# motherboard.net
KiCad netlist of a schematic drawn in EAGLE
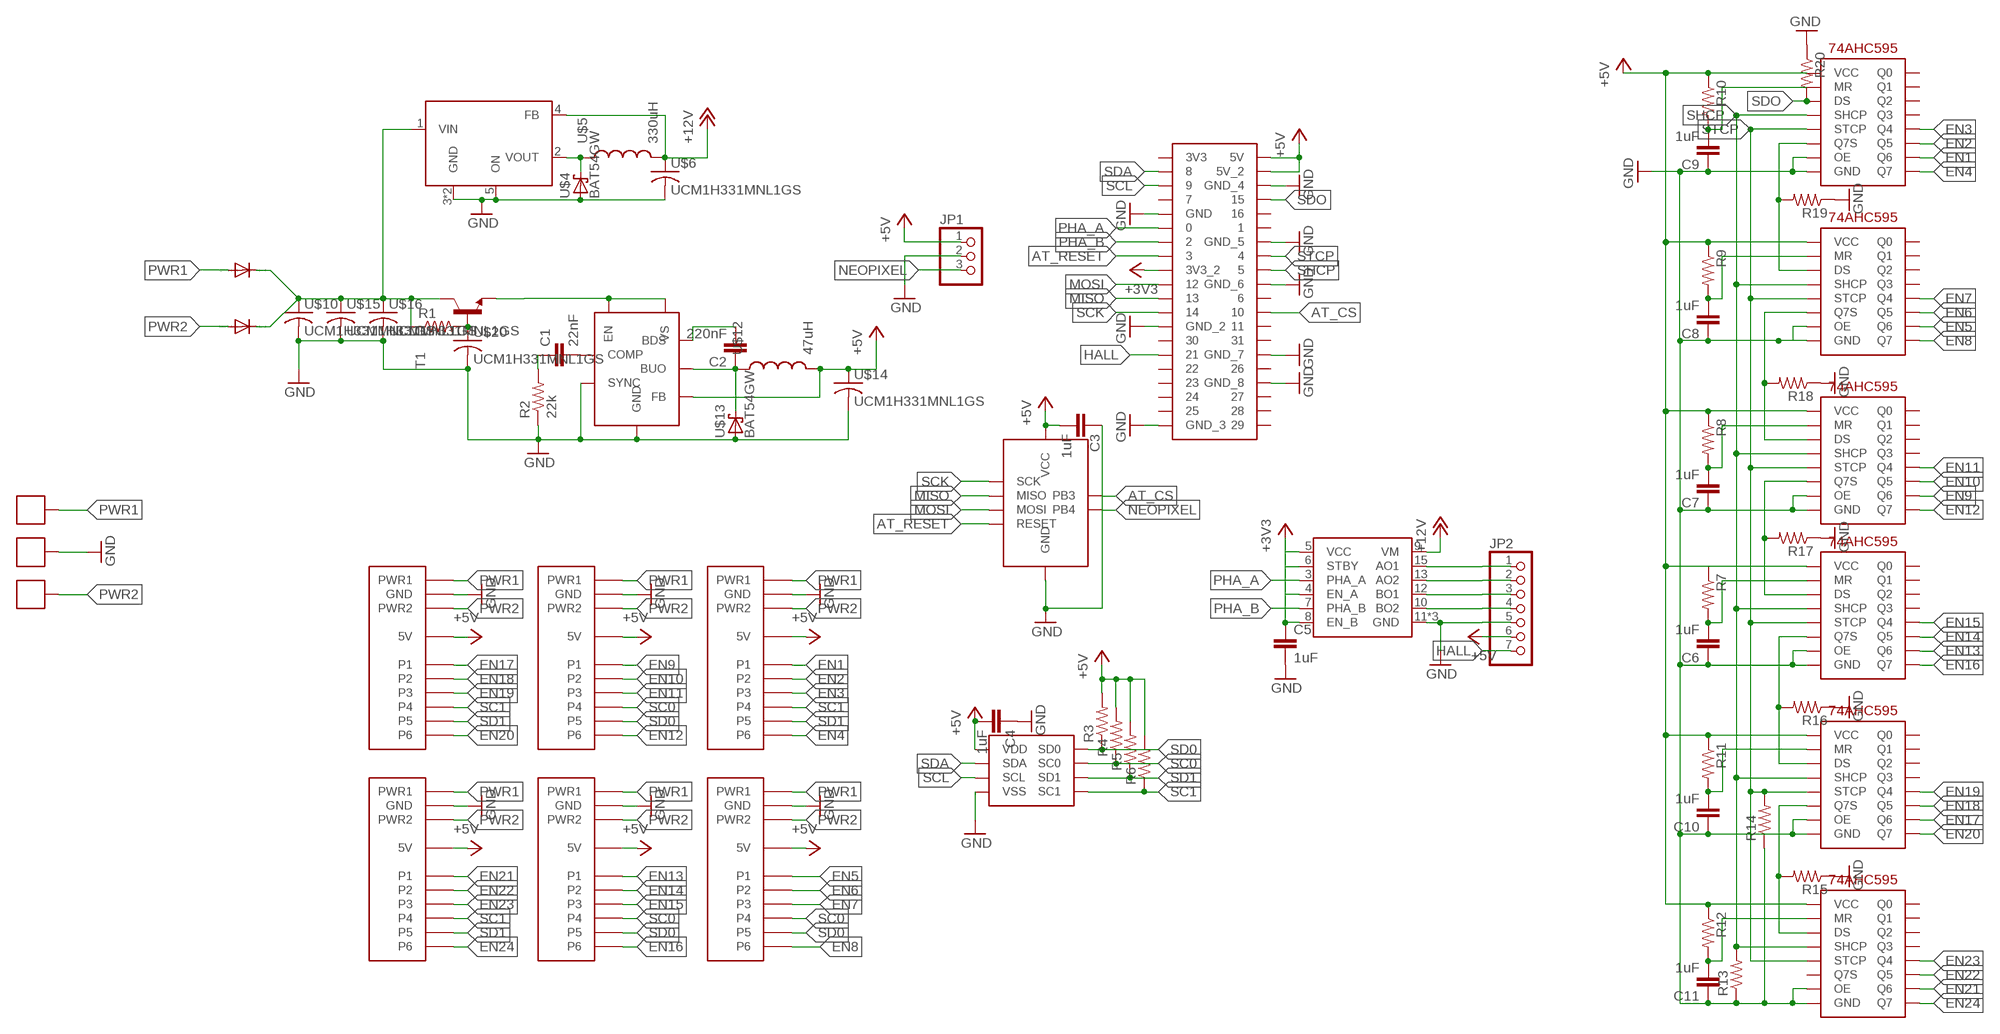
[diagram p0: schematic, sheet 1]

(export (version "E")
  (design (tool "Eeschema 10.0.6"))
  (components
    (comp (ref "B1")
      (value "PCIE_SOCKET")
      (footprint "eagle-import:PCIE_SOCKET")
      (libsource (lib "eagle-import") (part "PCIE_SOCKET"))
    )
    (comp (ref "B2")
      (value "PCIE_SOCKET")
      (footprint "eagle-import:PCIE_SOCKET")
      (libsource (lib "eagle-import") (part "PCIE_SOCKET"))
    )
    (comp (ref "B3")
      (value "PCIE_SOCKET")
      (footprint "eagle-import:PCIE_SOCKET")
      (libsource (lib "eagle-import") (part "PCIE_SOCKET"))
    )
    (comp (ref "B4")
      (value "PCIE_SOCKET")
      (footprint "eagle-import:PCIE_SOCKET")
      (libsource (lib "eagle-import") (part "PCIE_SOCKET"))
    )
    (comp (ref "B5")
      (value "PCIE_SOCKET")
      (footprint "eagle-import:PCIE_SOCKET")
      (libsource (lib "eagle-import") (part "PCIE_SOCKET"))
    )
    (comp (ref "B6")
      (value "PCIE_SOCKET")
      (footprint "eagle-import:PCIE_SOCKET")
      (libsource (lib "eagle-import") (part "PCIE_SOCKET"))
    )
    (comp (ref "C1")
      (value "22nF")
      (footprint "eagle-import:C0805")
      (libsource (lib "eagle-import") (part "C-EUC0805"))
    )
    (comp (ref "C2")
      (value "220nF")
      (footprint "eagle-import:C0805")
      (libsource (lib "eagle-import") (part "C-EUC0805"))
    )
    (comp (ref "C3")
      (value "1uF")
      (footprint "eagle-import:C0805")
      (libsource (lib "eagle-import") (part "C-EUC0805"))
    )
    (comp (ref "C4")
      (value "1uF")
      (footprint "eagle-import:C0805")
      (libsource (lib "eagle-import") (part "C-EUC0805"))
    )
    (comp (ref "C5")
      (value "1uF")
      (footprint "eagle-import:C0805")
      (libsource (lib "eagle-import") (part "C-EUC0805"))
    )
    (comp (ref "C6")
      (value "1uF")
      (footprint "eagle-import:C0805")
      (libsource (lib "eagle-import") (part "C-EUC0805"))
    )
    (comp (ref "C7")
      (value "1uF")
      (footprint "eagle-import:C0805")
      (libsource (lib "eagle-import") (part "C-EUC0805"))
    )
    (comp (ref "C8")
      (value "1uF")
      (footprint "eagle-import:C0805")
      (libsource (lib "eagle-import") (part "C-EUC0805"))
    )
    (comp (ref "C9")
      (value "1uF")
      (footprint "eagle-import:C0805")
      (libsource (lib "eagle-import") (part "C-EUC0805"))
    )
    (comp (ref "C10")
      (value "1uF")
      (footprint "eagle-import:C0805")
      (libsource (lib "eagle-import") (part "C-EUC0805"))
    )
    (comp (ref "C11")
      (value "1uF")
      (footprint "eagle-import:C0805")
      (libsource (lib "eagle-import") (part "C-EUC0805"))
    )
    (comp (ref "JP1")
      (value "PINHD-1X3")
      (footprint "eagle-import:1X03")
      (libsource (lib "eagle-import") (part "PINHD-1X3"))
    )
    (comp (ref "JP2")
      (value "PINHD-1X7")
      (footprint "eagle-import:1X07")
      (libsource (lib "eagle-import") (part "PINHD-1X7"))
    )
    (comp (ref "R1")
      (value "R-US_R1206")
      (footprint "eagle-import:R1206")
      (libsource (lib "eagle-import") (part "R-US_R1206"))
    )
    (comp (ref "R2")
      (value "22k")
      (footprint "eagle-import:R1206")
      (libsource (lib "eagle-import") (part "R-US_R1206"))
    )
    (comp (ref "R3")
      (value "R-US_R0805")
      (footprint "eagle-import:R0805")
      (libsource (lib "eagle-import") (part "R-US_R0805"))
    )
    (comp (ref "R4")
      (value "R-US_R0805")
      (footprint "eagle-import:R0805")
      (libsource (lib "eagle-import") (part "R-US_R0805"))
    )
    (comp (ref "R5")
      (value "R-US_R0805")
      (footprint "eagle-import:R0805")
      (libsource (lib "eagle-import") (part "R-US_R0805"))
    )
    (comp (ref "R6")
      (value "R-US_R0805")
      (footprint "eagle-import:R0805")
      (libsource (lib "eagle-import") (part "R-US_R0805"))
    )
    (comp (ref "R7")
      (value "R-US_R0805")
      (footprint "eagle-import:R0805")
      (libsource (lib "eagle-import") (part "R-US_R0805"))
    )
    (comp (ref "R8")
      (value "R-US_R0805")
      (footprint "eagle-import:R0805")
      (libsource (lib "eagle-import") (part "R-US_R0805"))
    )
    (comp (ref "R9")
      (value "R-US_R0805")
      (footprint "eagle-import:R0805")
      (libsource (lib "eagle-import") (part "R-US_R0805"))
    )
    (comp (ref "R10")
      (value "R-US_R0805")
      (footprint "eagle-import:R0805")
      (libsource (lib "eagle-import") (part "R-US_R0805"))
    )
    (comp (ref "R11")
      (value "R-US_R0805")
      (footprint "eagle-import:R0805")
      (libsource (lib "eagle-import") (part "R-US_R0805"))
    )
    (comp (ref "R12")
      (value "R-US_R0805")
      (footprint "eagle-import:R0805")
      (libsource (lib "eagle-import") (part "R-US_R0805"))
    )
    (comp (ref "R13")
      (value "R-US_R0805")
      (footprint "eagle-import:R0805")
      (libsource (lib "eagle-import") (part "R-US_R0805"))
    )
    (comp (ref "R14")
      (value "R-US_R0805")
      (footprint "eagle-import:R0805")
      (libsource (lib "eagle-import") (part "R-US_R0805"))
    )
    (comp (ref "R15")
      (value "R-US_R0805")
      (footprint "eagle-import:R0805")
      (libsource (lib "eagle-import") (part "R-US_R0805"))
    )
    (comp (ref "R16")
      (value "R-US_R0805")
      (footprint "eagle-import:R0805")
      (libsource (lib "eagle-import") (part "R-US_R0805"))
    )
    (comp (ref "R17")
      (value "R-US_R0805")
      (footprint "eagle-import:R0805")
      (libsource (lib "eagle-import") (part "R-US_R0805"))
    )
    (comp (ref "R18")
      (value "R-US_R0805")
      (footprint "eagle-import:R0805")
      (libsource (lib "eagle-import") (part "R-US_R0805"))
    )
    (comp (ref "R19")
      (value "R-US_R0805")
      (footprint "eagle-import:R0805")
      (libsource (lib "eagle-import") (part "R-US_R0805"))
    )
    (comp (ref "R20")
      (value "R-US_R0805")
      (footprint "eagle-import:R0805")
      (libsource (lib "eagle-import") (part "R-US_R0805"))
    )
    (comp (ref "T1")
      (value "-NPN-SOT23-EBC")
      (footprint "eagle-import:SOT23-EBC")
      (libsource (lib "eagle-import") (part "-NPN-SOT23-EBC"))
    )
    (comp (ref "U$1")
      (value "RPI_SOCKET")
      (footprint "eagle-import:40PIN_SOCKET")
      (libsource (lib "eagle-import") (part "RPI_SOCKET"))
    )
    (comp (ref "U$2")
      (value "TC78H620FNG")
      (footprint "eagle-import:SSOP16")
      (libsource (lib "eagle-import") (part "TC78H620FNG"))
    )
    (comp (ref "U$3")
      (value "TL2575HV-12IKTTR")
      (footprint "eagle-import:TO170P1524X483-6")
      (libsource (lib "eagle-import") (part "TL2575HV-12IKTTR"))
    )
    (comp (ref "U$4")
      (value "BAT54GW")
      (footprint "eagle-import:SOD3616X130")
      (libsource (lib "eagle-import") (part "BAT54GW"))
    )
    (comp (ref "U$5")
      (value "330uH")
      (footprint "eagle-import:SRN8040TA")
      (libsource (lib "eagle-import") (part "SRN8040TA"))
    )
    (comp (ref "U$6")
      (value "UCM1H331MNL1GS")
      (footprint "eagle-import:CAPAE1030X1050")
      (libsource (lib "eagle-import") (part "UCM1H331MNL1GS"))
    )
    (comp (ref "U$7")
      (value "74HC595_QFN")
      (footprint "eagle-import:QFN50P250X350X100-16")
      (libsource (lib "eagle-import") (part "74HC595_QFN"))
    )
    (comp (ref "U$8")
      (value "BAS16GW")
      (footprint "eagle-import:SOD3616X130")
      (libsource (lib "eagle-import") (part "BAS16GW"))
    )
    (comp (ref "U$9")
      (value "BAS16GW")
      (footprint "eagle-import:SOD3616X130")
      (libsource (lib "eagle-import") (part "BAS16GW"))
    )
    (comp (ref "U$10")
      (value "UCM1H331MNL1GS")
      (footprint "eagle-import:CAPAE1030X1050")
      (libsource (lib "eagle-import") (part "UCM1H331MNL1GS"))
    )
    (comp (ref "U$11")
      (value "ATTINY85")
      (footprint "eagle-import:SOIC127P599X175-8")
      (libsource (lib "eagle-import") (part "ATTINY85"))
    )
    (comp (ref "U$12")
      (value "47uH")
      (footprint "eagle-import:SRN8040TA")
      (libsource (lib "eagle-import") (part "SRN8040TA"))
    )
    (comp (ref "U$13")
      (value "BAT54GW")
      (footprint "eagle-import:SOD3616X130")
      (libsource (lib "eagle-import") (part "BAT54GW"))
    )
    (comp (ref "U$14")
      (value "UCM1H331MNL1GS")
      (footprint "eagle-import:CAPAE1030X1050")
      (libsource (lib "eagle-import") (part "UCM1H331MNL1GS"))
    )
    (comp (ref "U$15")
      (value "UCM1H331MNL1GS")
      (footprint "eagle-import:CAPAE1030X1050")
      (libsource (lib "eagle-import") (part "UCM1H331MNL1GS"))
    )
    (comp (ref "U$16")
      (value "UCM1H331MNL1GS")
      (footprint "eagle-import:CAPAE1030X1050")
      (libsource (lib "eagle-import") (part "UCM1H331MNL1GS"))
    )
    (comp (ref "U$17")
      (value "1935310")
      (footprint "eagle-import:1935310")
      (libsource (lib "eagle-import") (part "1935310"))
    )
    (comp (ref "U$18")
      (value "1935310")
      (footprint "eagle-import:1935310")
      (libsource (lib "eagle-import") (part "1935310"))
    )
    (comp (ref "U$19")
      (value "1935310")
      (footprint "eagle-import:1935310")
      (libsource (lib "eagle-import") (part "1935310"))
    )
    (comp (ref "U$20")
      (value "UCM1H331MNL1GS")
      (footprint "eagle-import:CAPAE1030X1050")
      (libsource (lib "eagle-import") (part "UCM1H331MNL1GS"))
    )
    (comp (ref "U$21")
      (value "PCA9540BDP")
      (footprint "eagle-import:TSSOP8")
      (libsource (lib "eagle-import") (part "PCA9540BDP"))
    )
    (comp (ref "U$22")
      (value "74HC595_QFN")
      (footprint "eagle-import:QFN50P250X350X100-16")
      (libsource (lib "eagle-import") (part "74HC595_QFN"))
    )
    (comp (ref "U$23")
      (value "74HC595_QFN")
      (footprint "eagle-import:QFN50P250X350X100-16")
      (libsource (lib "eagle-import") (part "74HC595_QFN"))
    )
    (comp (ref "U$24")
      (value "74HC595_QFN")
      (footprint "eagle-import:QFN50P250X350X100-16")
      (libsource (lib "eagle-import") (part "74HC595_QFN"))
    )
    (comp (ref "U$25")
      (value "74HC595_QFN")
      (footprint "eagle-import:QFN50P250X350X100-16")
      (libsource (lib "eagle-import") (part "74HC595_QFN"))
    )
    (comp (ref "U$26")
      (value "74HC595_QFN")
      (footprint "eagle-import:QFN50P250X350X100-16")
      (libsource (lib "eagle-import") (part "74HC595_QFN"))
    )
    (comp (ref "U1")
      (value "IFX91041EJV50XUMA1")
      (footprint "eagle-import:SOIC127P600X170-8")
      (libsource (lib "eagle-import") (part "IFX91041EJV50XUMA1"))
    )
  )
  (nets
    (net (code "1") (name "+3V3") (class "Default")
      (node (ref "C5") (pin "1") (pinfunction "1_1") (pintype "passive"))
      (node (ref "U$1") (pin "P17") (pinfunction "3V3_2_P17") (pintype "bidirectional"))
      (node (ref "U$2") (pin "4") (pinfunction "EN_A_4") (pintype "bidirectional"))
      (node (ref "U$2") (pin "5") (pinfunction "VCC_5") (pintype "bidirectional"))
      (node (ref "U$2") (pin "6") (pinfunction "STBY_6") (pintype "bidirectional"))
      (node (ref "U$2") (pin "8") (pinfunction "EN_B_8") (pintype "bidirectional"))
    )
    (net (code "2") (name "+5V") (class "Default")
      (node (ref "B1") (pin "5V_1") (pinfunction "5V_5V_1") (pintype "passive"))
      (node (ref "B1") (pin "5V_2") (pinfunction "5V_5V_2") (pintype "passive"))
      (node (ref "B2") (pin "5V_1") (pinfunction "5V_5V_1") (pintype "passive"))
      (node (ref "B2") (pin "5V_2") (pinfunction "5V_5V_2") (pintype "passive"))
      (node (ref "B3") (pin "5V_1") (pinfunction "5V_5V_1") (pintype "passive"))
      (node (ref "B3") (pin "5V_2") (pinfunction "5V_5V_2") (pintype "passive"))
      (node (ref "B4") (pin "5V_1") (pinfunction "5V_5V_1") (pintype "passive"))
      (node (ref "B4") (pin "5V_2") (pinfunction "5V_5V_2") (pintype "passive"))
      (node (ref "B5") (pin "5V_1") (pinfunction "5V_5V_1") (pintype "passive"))
      (node (ref "B5") (pin "5V_2") (pinfunction "5V_5V_2") (pintype "passive"))
      (node (ref "B6") (pin "5V_1") (pinfunction "5V_5V_1") (pintype "passive"))
      (node (ref "B6") (pin "5V_2") (pinfunction "5V_5V_2") (pintype "passive"))
      (node (ref "C3") (pin "2") (pinfunction "2_2") (pintype "passive"))
      (node (ref "C4") (pin "2") (pinfunction "2_2") (pintype "passive"))
      (node (ref "JP1") (pin "1") (pinfunction "1_1") (pintype "passive"))
      (node (ref "JP2") (pin "6") (pinfunction "6_6") (pintype "passive"))
      (node (ref "R10") (pin "1") (pinfunction "1_1") (pintype "passive"))
      (node (ref "R11") (pin "1") (pinfunction "1_1") (pintype "passive"))
      (node (ref "R12") (pin "1") (pinfunction "1_1") (pintype "passive"))
      (node (ref "R3") (pin "2") (pinfunction "2_2") (pintype "passive"))
      (node (ref "R4") (pin "2") (pinfunction "2_2") (pintype "passive"))
      (node (ref "R5") (pin "2") (pinfunction "2_2") (pintype "passive"))
      (node (ref "R6") (pin "2") (pinfunction "2_2") (pintype "passive"))
      (node (ref "R7") (pin "1") (pinfunction "1_1") (pintype "passive"))
      (node (ref "R8") (pin "1") (pinfunction "1_1") (pintype "passive"))
      (node (ref "R9") (pin "1") (pinfunction "1_1") (pintype "passive"))
      (node (ref "U$1") (pin "P2") (pinfunction "5V_P2") (pintype "bidirectional"))
      (node (ref "U$1") (pin "P4") (pinfunction "5V_2_P4") (pintype "bidirectional"))
      (node (ref "U$11") (pin "8") (pinfunction "VCC_8") (pintype "bidirectional"))
      (node (ref "U$12") (pin "P$2") (pinfunction "2_P$2") (pintype "passive"))
      (node (ref "U$14") (pin "1") (pinfunction "1_1") (pintype "passive"))
      (node (ref "U$21") (pin "3") (pinfunction "VDD_3") (pintype "bidirectional"))
      (node (ref "U$22") (pin "P16") (pinfunction "VCC_P16") (pintype "bidirectional"))
      (node (ref "U$23") (pin "P16") (pinfunction "VCC_P16") (pintype "bidirectional"))
      (node (ref "U$24") (pin "P16") (pinfunction "VCC_P16") (pintype "bidirectional"))
      (node (ref "U$25") (pin "P16") (pinfunction "VCC_P16") (pintype "bidirectional"))
      (node (ref "U$26") (pin "P16") (pinfunction "VCC_P16") (pintype "bidirectional"))
      (node (ref "U$7") (pin "P16") (pinfunction "VCC_P16") (pintype "bidirectional"))
      (node (ref "U1") (pin "4") (pinfunction "FB_4") (pintype "bidirectional"))
    )
    (net (code "3") (name "+12V") (class "Default")
      (node (ref "U$2") (pin "9") (pinfunction "VM_9") (pintype "bidirectional"))
      (node (ref "U$3") (pin "4") (pinfunction "FB_4") (pintype "bidirectional"))
      (node (ref "U$5") (pin "P$2") (pinfunction "2_P$2") (pintype "passive"))
      (node (ref "U$6") (pin "1") (pinfunction "1_1") (pintype "passive"))
    )
    (net (code "4") (name "AT_CS") (class "Default")
      (node (ref "U$1") (pin "P24") (pinfunction "10_P24") (pintype "bidirectional"))
      (node (ref "U$11") (pin "2") (pinfunction "PB3_2") (pintype "bidirectional"))
    )
    (net (code "5") (name "AT_RESET") (class "Default")
      (node (ref "U$1") (pin "P15") (pinfunction "3_P15") (pintype "bidirectional"))
      (node (ref "U$11") (pin "1") (pinfunction "RESET_1") (pintype "bidirectional"))
    )
    (net (code "6") (name "EN1") (class "Default")
      (node (ref "B1") (pin "P1") (pinfunction "P1_P1") (pintype "bidirectional"))
      (node (ref "U$7") (pin "P6") (pinfunction "Q6_P6") (pintype "bidirectional"))
    )
    (net (code "7") (name "EN2") (class "Default")
      (node (ref "B1") (pin "P2") (pinfunction "P2_P2") (pintype "bidirectional"))
      (node (ref "U$7") (pin "P5") (pinfunction "Q5_P5") (pintype "bidirectional"))
    )
    (net (code "8") (name "EN3") (class "Default")
      (node (ref "B1") (pin "P3") (pinfunction "P3_P3") (pintype "bidirectional"))
      (node (ref "U$7") (pin "P4") (pinfunction "Q4_P4") (pintype "bidirectional"))
    )
    (net (code "9") (name "EN4") (class "Default")
      (node (ref "B1") (pin "P6") (pinfunction "P6_P6") (pintype "bidirectional"))
      (node (ref "U$7") (pin "P7") (pinfunction "Q7_P7") (pintype "bidirectional"))
    )
    (net (code "10") (name "EN5") (class "Default")
      (node (ref "B2") (pin "P1") (pinfunction "P1_P1") (pintype "bidirectional"))
      (node (ref "U$22") (pin "P6") (pinfunction "Q6_P6") (pintype "bidirectional"))
    )
    (net (code "11") (name "EN6") (class "Default")
      (node (ref "B2") (pin "P2") (pinfunction "P2_P2") (pintype "bidirectional"))
      (node (ref "U$22") (pin "P5") (pinfunction "Q5_P5") (pintype "bidirectional"))
    )
    (net (code "12") (name "EN7") (class "Default")
      (node (ref "B2") (pin "P3") (pinfunction "P3_P3") (pintype "bidirectional"))
      (node (ref "U$22") (pin "P4") (pinfunction "Q4_P4") (pintype "bidirectional"))
    )
    (net (code "13") (name "EN8") (class "Default")
      (node (ref "B2") (pin "P6") (pinfunction "P6_P6") (pintype "bidirectional"))
      (node (ref "U$22") (pin "P7") (pinfunction "Q7_P7") (pintype "bidirectional"))
    )
    (net (code "14") (name "EN9") (class "Default")
      (node (ref "B3") (pin "P1") (pinfunction "P1_P1") (pintype "bidirectional"))
      (node (ref "U$23") (pin "P6") (pinfunction "Q6_P6") (pintype "bidirectional"))
    )
    (net (code "15") (name "EN10") (class "Default")
      (node (ref "B3") (pin "P2") (pinfunction "P2_P2") (pintype "bidirectional"))
      (node (ref "U$23") (pin "P5") (pinfunction "Q5_P5") (pintype "bidirectional"))
    )
    (net (code "16") (name "EN11") (class "Default")
      (node (ref "B3") (pin "P3") (pinfunction "P3_P3") (pintype "bidirectional"))
      (node (ref "U$23") (pin "P4") (pinfunction "Q4_P4") (pintype "bidirectional"))
    )
    (net (code "17") (name "EN12") (class "Default")
      (node (ref "B3") (pin "P6") (pinfunction "P6_P6") (pintype "bidirectional"))
      (node (ref "U$23") (pin "P7") (pinfunction "Q7_P7") (pintype "bidirectional"))
    )
    (net (code "18") (name "EN13") (class "Default")
      (node (ref "B4") (pin "P1") (pinfunction "P1_P1") (pintype "bidirectional"))
      (node (ref "U$24") (pin "P6") (pinfunction "Q6_P6") (pintype "bidirectional"))
    )
    (net (code "19") (name "EN14") (class "Default")
      (node (ref "B4") (pin "P2") (pinfunction "P2_P2") (pintype "bidirectional"))
      (node (ref "U$24") (pin "P5") (pinfunction "Q5_P5") (pintype "bidirectional"))
    )
    (net (code "20") (name "EN15") (class "Default")
      (node (ref "B4") (pin "P3") (pinfunction "P3_P3") (pintype "bidirectional"))
      (node (ref "U$24") (pin "P4") (pinfunction "Q4_P4") (pintype "bidirectional"))
    )
    (net (code "21") (name "EN16") (class "Default")
      (node (ref "B4") (pin "P6") (pinfunction "P6_P6") (pintype "bidirectional"))
      (node (ref "U$24") (pin "P7") (pinfunction "Q7_P7") (pintype "bidirectional"))
    )
    (net (code "22") (name "EN17") (class "Default")
      (node (ref "B5") (pin "P1") (pinfunction "P1_P1") (pintype "bidirectional"))
      (node (ref "U$25") (pin "P6") (pinfunction "Q6_P6") (pintype "bidirectional"))
    )
    (net (code "23") (name "EN18") (class "Default")
      (node (ref "B5") (pin "P2") (pinfunction "P2_P2") (pintype "bidirectional"))
      (node (ref "U$25") (pin "P5") (pinfunction "Q5_P5") (pintype "bidirectional"))
    )
    (net (code "24") (name "EN19") (class "Default")
      (node (ref "B5") (pin "P3") (pinfunction "P3_P3") (pintype "bidirectional"))
      (node (ref "U$25") (pin "P4") (pinfunction "Q4_P4") (pintype "bidirectional"))
    )
    (net (code "25") (name "EN20") (class "Default")
      (node (ref "B5") (pin "P6") (pinfunction "P6_P6") (pintype "bidirectional"))
      (node (ref "U$25") (pin "P7") (pinfunction "Q7_P7") (pintype "bidirectional"))
    )
    (net (code "26") (name "EN21") (class "Default")
      (node (ref "B6") (pin "P1") (pinfunction "P1_P1") (pintype "bidirectional"))
      (node (ref "U$26") (pin "P6") (pinfunction "Q6_P6") (pintype "bidirectional"))
    )
    (net (code "27") (name "EN22") (class "Default")
      (node (ref "B6") (pin "P2") (pinfunction "P2_P2") (pintype "bidirectional"))
      (node (ref "U$26") (pin "P5") (pinfunction "Q5_P5") (pintype "bidirectional"))
    )
    (net (code "28") (name "EN23") (class "Default")
      (node (ref "B6") (pin "P3") (pinfunction "P3_P3") (pintype "bidirectional"))
      (node (ref "U$26") (pin "P4") (pinfunction "Q4_P4") (pintype "bidirectional"))
    )
    (net (code "29") (name "EN24") (class "Default")
      (node (ref "B6") (pin "P6") (pinfunction "P6_P6") (pintype "bidirectional"))
      (node (ref "U$26") (pin "P7") (pinfunction "Q7_P7") (pintype "bidirectional"))
    )
    (net (code "30") (name "GND") (class "Default")
      (node (ref "B1") (pin "GND1") (pinfunction "GND_GND1") (pintype "passive"))
      (node (ref "B1") (pin "GND2") (pinfunction "GND_GND2") (pintype "passive"))
      (node (ref "B2") (pin "GND1") (pinfunction "GND_GND1") (pintype "passive"))
      (node (ref "B2") (pin "GND2") (pinfunction "GND_GND2") (pintype "passive"))
      (node (ref "B3") (pin "GND1") (pinfunction "GND_GND1") (pintype "passive"))
      (node (ref "B3") (pin "GND2") (pinfunction "GND_GND2") (pintype "passive"))
      (node (ref "B4") (pin "GND1") (pinfunction "GND_GND1") (pintype "passive"))
      (node (ref "B4") (pin "GND2") (pinfunction "GND_GND2") (pintype "passive"))
      (node (ref "B5") (pin "GND1") (pinfunction "GND_GND1") (pintype "passive"))
      (node (ref "B5") (pin "GND2") (pinfunction "GND_GND2") (pintype "passive"))
      (node (ref "B6") (pin "GND1") (pinfunction "GND_GND1") (pintype "passive"))
      (node (ref "B6") (pin "GND2") (pinfunction "GND_GND2") (pintype "passive"))
      (node (ref "C10") (pin "1") (pinfunction "1_1") (pintype "passive"))
      (node (ref "C11") (pin "1") (pinfunction "1_1") (pintype "passive"))
      (node (ref "C3") (pin "1") (pinfunction "1_1") (pintype "passive"))
      (node (ref "C4") (pin "1") (pinfunction "1_1") (pintype "passive"))
      (node (ref "C5") (pin "2") (pinfunction "2_2") (pintype "passive"))
      (node (ref "C6") (pin "1") (pinfunction "1_1") (pintype "passive"))
      (node (ref "C7") (pin "1") (pinfunction "1_1") (pintype "passive"))
      (node (ref "C8") (pin "1") (pinfunction "1_1") (pintype "passive"))
      (node (ref "C9") (pin "1") (pinfunction "1_1") (pintype "passive"))
      (node (ref "JP1") (pin "2") (pinfunction "2_2") (pintype "passive"))
      (node (ref "JP2") (pin "5") (pinfunction "5_5") (pintype "passive"))
      (node (ref "R13") (pin "1") (pinfunction "1_1") (pintype "passive"))
      (node (ref "R14") (pin "1") (pinfunction "1_1") (pintype "passive"))
      (node (ref "R15") (pin "1") (pinfunction "1_1") (pintype "passive"))
      (node (ref "R16") (pin "1") (pinfunction "1_1") (pintype "passive"))
      (node (ref "R17") (pin "1") (pinfunction "1_1") (pintype "passive"))
      (node (ref "R18") (pin "1") (pinfunction "1_1") (pintype "passive"))
      (node (ref "R19") (pin "1") (pinfunction "1_1") (pintype "passive"))
      (node (ref "R2") (pin "1") (pinfunction "1_1") (pintype "passive"))
      (node (ref "R20") (pin "1") (pinfunction "1_1") (pintype "passive"))
      (node (ref "U$1") (pin "P14") (pinfunction "GND_5_P14") (pintype "bidirectional"))
      (node (ref "U$1") (pin "P20") (pinfunction "GND_6_P20") (pintype "bidirectional"))
      (node (ref "U$1") (pin "P25") (pinfunction "GND_2_P25") (pintype "bidirectional"))
      (node (ref "U$1") (pin "P30") (pinfunction "GND_7_P30") (pintype "bidirectional"))
      (node (ref "U$1") (pin "P34") (pinfunction "GND_8_P34") (pintype "bidirectional"))
      (node (ref "U$1") (pin "P39") (pinfunction "GND_3_P39") (pintype "bidirectional"))
      (node (ref "U$1") (pin "P6") (pinfunction "GND_4_P6") (pintype "bidirectional"))
      (node (ref "U$1") (pin "P9") (pinfunction "GND_P9") (pintype "bidirectional"))
      (node (ref "U$10") (pin "2") (pinfunction "2_2") (pintype "passive"))
      (node (ref "U$11") (pin "4") (pinfunction "GND_4") (pintype "bidirectional"))
      (node (ref "U$13") (pin "2") (pinfunction "A_2") (pintype "passive"))
      (node (ref "U$14") (pin "2") (pinfunction "2_2") (pintype "passive"))
      (node (ref "U$15") (pin "2") (pinfunction "2_2") (pintype "passive"))
      (node (ref "U$16") (pin "2") (pinfunction "2_2") (pintype "passive"))
      (node (ref "U$18") (pin "P$1") (pinfunction "P$1_P$1") (pintype "bidirectional"))
      (node (ref "U$18") (pin "P$2") (pinfunction "P$1_P$2") (pintype "bidirectional"))
      (node (ref "U$2") (pin "11") (pinfunction "GND_11") (pintype "bidirectional"))
      (node (ref "U$2") (pin "14") (pinfunction "GND_14") (pintype "bidirectional"))
      (node (ref "U$2") (pin "16") (pinfunction "GND_16") (pintype "bidirectional"))
      (node (ref "U$20") (pin "2") (pinfunction "2_2") (pintype "passive"))
      (node (ref "U$21") (pin "6") (pinfunction "VSS_6") (pintype "bidirectional"))
      (node (ref "U$22") (pin "P$1") (pinfunction "GND_P$1") (pintype "bidirectional"))
      (node (ref "U$22") (pin "P13") (pinfunction "OE_P13") (pintype "bidirectional"))
      (node (ref "U$22") (pin "P8") (pinfunction "GND_P8") (pintype "bidirectional"))
      (node (ref "U$23") (pin "P$1") (pinfunction "GND_P$1") (pintype "bidirectional"))
      (node (ref "U$23") (pin "P13") (pinfunction "OE_P13") (pintype "bidirectional"))
      (node (ref "U$23") (pin "P8") (pinfunction "GND_P8") (pintype "bidirectional"))
      (node (ref "U$24") (pin "P$1") (pinfunction "GND_P$1") (pintype "bidirectional"))
      (node (ref "U$24") (pin "P13") (pinfunction "OE_P13") (pintype "bidirectional"))
      (node (ref "U$24") (pin "P8") (pinfunction "GND_P8") (pintype "bidirectional"))
      (node (ref "U$25") (pin "P$1") (pinfunction "GND_P$1") (pintype "bidirectional"))
      (node (ref "U$25") (pin "P13") (pinfunction "OE_P13") (pintype "bidirectional"))
      (node (ref "U$25") (pin "P8") (pinfunction "GND_P8") (pintype "bidirectional"))
      (node (ref "U$26") (pin "P$1") (pinfunction "GND_P$1") (pintype "bidirectional"))
      (node (ref "U$26") (pin "P13") (pinfunction "OE_P13") (pintype "bidirectional"))
      (node (ref "U$26") (pin "P8") (pinfunction "GND_P8") (pintype "bidirectional"))
      (node (ref "U$3") (pin "3") (pinfunction "GND_3") (pintype "bidirectional"))
      (node (ref "U$3") (pin "5") (pinfunction "ON_5") (pintype "bidirectional"))
      (node (ref "U$3") (pin "6") (pinfunction "GND_6") (pintype "bidirectional"))
      (node (ref "U$4") (pin "2") (pinfunction "A_2") (pintype "passive"))
      (node (ref "U$6") (pin "2") (pinfunction "2_2") (pintype "passive"))
      (node (ref "U$7") (pin "P$1") (pinfunction "GND_P$1") (pintype "bidirectional"))
      (node (ref "U$7") (pin "P13") (pinfunction "OE_P13") (pintype "bidirectional"))
      (node (ref "U$7") (pin "P8") (pinfunction "GND_P8") (pintype "bidirectional"))
      (node (ref "U1") (pin "1") (pinfunction "SYNC_1") (pintype "bidirectional"))
      (node (ref "U1") (pin "2") (pinfunction "GND_2") (pintype "bidirectional"))
      (node (ref "U1") (pin "PAD") (pinfunction "GND_PAD") (pintype "bidirectional"))
    )
    (net (code "31") (name "HALL") (class "Default")
      (node (ref "JP2") (pin "7") (pinfunction "7_7") (pintype "passive"))
      (node (ref "U$1") (pin "P29") (pinfunction "21_P29") (pintype "bidirectional"))
    )
    (net (code "32") (name "MISO") (class "Default")
      (node (ref "U$1") (pin "P21") (pinfunction "13_P21") (pintype "bidirectional"))
      (node (ref "U$11") (pin "6") (pinfunction "MISO_6") (pintype "bidirectional"))
    )
    (net (code "33") (name "MOSI") (class "Default")
      (node (ref "U$1") (pin "P19") (pinfunction "12_P19") (pintype "bidirectional"))
      (node (ref "U$11") (pin "5") (pinfunction "MOSI_5") (pintype "bidirectional"))
    )
    (net (code "34") (name "NEOPIXEL") (class "Default")
      (node (ref "JP1") (pin "3") (pinfunction "3_3") (pintype "passive"))
      (node (ref "U$11") (pin "3") (pinfunction "PB4_3") (pintype "bidirectional"))
    )
    (net (code "35") (name "Net-(C1-Pad1)") (class "Default")
      (node (ref "C1") (pin "1") (pinfunction "1_1") (pintype "passive"))
      (node (ref "R2") (pin "2") (pinfunction "2_2") (pintype "passive"))
    )
    (net (code "36") (name "Net-(R1-Pad2)") (class "Default")
      (node (ref "R1") (pin "2") (pinfunction "2_2") (pintype "passive"))
      (node (ref "T1") (pin "B") (pinfunction "B_B") (pintype "passive"))
      (node (ref "U$20") (pin "1") (pinfunction "1_1") (pintype "passive"))
    )
    (net (code "37") (name "Net-(U$2-AO1)") (class "Default")
      (node (ref "JP2") (pin "1") (pinfunction "1_1") (pintype "passive"))
      (node (ref "U$2") (pin "15") (pinfunction "AO1_15") (pintype "bidirectional"))
    )
    (net (code "38") (name "Net-(U$2-AO2)") (class "Default")
      (node (ref "JP2") (pin "2") (pinfunction "2_2") (pintype "passive"))
      (node (ref "U$2") (pin "13") (pinfunction "AO2_13") (pintype "bidirectional"))
    )
    (net (code "39") (name "Net-(U$2-BO1)") (class "Default")
      (node (ref "JP2") (pin "3") (pinfunction "3_3") (pintype "passive"))
      (node (ref "U$2") (pin "12") (pinfunction "BO1_12") (pintype "bidirectional"))
    )
    (net (code "40") (name "Net-(U$2-BO2)") (class "Default")
      (node (ref "JP2") (pin "4") (pinfunction "4_4") (pintype "passive"))
      (node (ref "U$2") (pin "10") (pinfunction "BO2_10") (pintype "bidirectional"))
    )
    (net (code "41") (name "Net-(U$3-VIN)") (class "Default")
      (node (ref "R1") (pin "1") (pinfunction "1_1") (pintype "passive"))
      (node (ref "T1") (pin "C") (pinfunction "C_C") (pintype "passive"))
      (node (ref "U$10") (pin "1") (pinfunction "1_1") (pintype "passive"))
      (node (ref "U$15") (pin "1") (pinfunction "1_1") (pintype "passive"))
      (node (ref "U$16") (pin "1") (pinfunction "1_1") (pintype "passive"))
      (node (ref "U$3") (pin "1") (pinfunction "VIN_1") (pintype "bidirectional"))
      (node (ref "U$8") (pin "1") (pinfunction "C_1") (pintype "passive"))
      (node (ref "U$9") (pin "1") (pinfunction "C_1") (pintype "passive"))
    )
    (net (code "42") (name "Net-(U$3-VOUT)") (class "Default")
      (node (ref "U$3") (pin "2") (pinfunction "VOUT_2") (pintype "bidirectional"))
      (node (ref "U$4") (pin "1") (pinfunction "C_1") (pintype "passive"))
      (node (ref "U$5") (pin "P$1") (pinfunction "1_P$1") (pintype "passive"))
    )
    (net (code "43") (name "Net-(U$7-MR)") (class "Default")
      (node (ref "C9") (pin "2") (pinfunction "2_2") (pintype "passive"))
      (node (ref "R10") (pin "2") (pinfunction "2_2") (pintype "passive"))
      (node (ref "U$7") (pin "P10") (pinfunction "MR_P10") (pintype "bidirectional"))
    )
    (net (code "44") (name "Net-(U$12-1)") (class "Default")
      (node (ref "C2") (pin "1") (pinfunction "1_1") (pintype "passive"))
      (node (ref "U$12") (pin "P$1") (pinfunction "1_P$1") (pintype "passive"))
      (node (ref "U$13") (pin "1") (pinfunction "C_1") (pintype "passive"))
      (node (ref "U1") (pin "6") (pinfunction "BUO_6") (pintype "bidirectional"))
    )
    (net (code "45") (name "Net-(U$22-DS)") (class "Default")
      (node (ref "R19") (pin "2") (pinfunction "2_2") (pintype "passive"))
      (node (ref "U$22") (pin "P14") (pinfunction "DS_P14") (pintype "bidirectional"))
      (node (ref "U$7") (pin "P9") (pinfunction "Q7S_P9") (pintype "bidirectional"))
    )
    (net (code "46") (name "Net-(U$22-MR)") (class "Default")
      (node (ref "C8") (pin "2") (pinfunction "2_2") (pintype "passive"))
      (node (ref "R9") (pin "2") (pinfunction "2_2") (pintype "passive"))
      (node (ref "U$22") (pin "P10") (pinfunction "MR_P10") (pintype "bidirectional"))
    )
    (net (code "47") (name "Net-(U$22-Q7S)") (class "Default")
      (node (ref "R18") (pin "2") (pinfunction "2_2") (pintype "passive"))
      (node (ref "U$22") (pin "P9") (pinfunction "Q7S_P9") (pintype "bidirectional"))
      (node (ref "U$23") (pin "P14") (pinfunction "DS_P14") (pintype "bidirectional"))
    )
    (net (code "48") (name "Net-(U$23-MR)") (class "Default")
      (node (ref "C7") (pin "2") (pinfunction "2_2") (pintype "passive"))
      (node (ref "R8") (pin "2") (pinfunction "2_2") (pintype "passive"))
      (node (ref "U$23") (pin "P10") (pinfunction "MR_P10") (pintype "bidirectional"))
    )
    (net (code "49") (name "Net-(U$23-Q7S)") (class "Default")
      (node (ref "R17") (pin "2") (pinfunction "2_2") (pintype "passive"))
      (node (ref "U$23") (pin "P9") (pinfunction "Q7S_P9") (pintype "bidirectional"))
      (node (ref "U$24") (pin "P14") (pinfunction "DS_P14") (pintype "bidirectional"))
    )
    (net (code "50") (name "Net-(U$24-MR)") (class "Default")
      (node (ref "C6") (pin "2") (pinfunction "2_2") (pintype "passive"))
      (node (ref "R7") (pin "2") (pinfunction "2_2") (pintype "passive"))
      (node (ref "U$24") (pin "P10") (pinfunction "MR_P10") (pintype "bidirectional"))
    )
    (net (code "51") (name "Net-(U$24-Q7S)") (class "Default")
      (node (ref "R16") (pin "2") (pinfunction "2_2") (pintype "passive"))
      (node (ref "U$24") (pin "P9") (pinfunction "Q7S_P9") (pintype "bidirectional"))
      (node (ref "U$25") (pin "P14") (pinfunction "DS_P14") (pintype "bidirectional"))
    )
    (net (code "52") (name "Net-(U$25-MR)") (class "Default")
      (node (ref "C10") (pin "2") (pinfunction "2_2") (pintype "passive"))
      (node (ref "R11") (pin "2") (pinfunction "2_2") (pintype "passive"))
      (node (ref "U$25") (pin "P10") (pinfunction "MR_P10") (pintype "bidirectional"))
    )
    (net (code "53") (name "Net-(U$25-Q7S)") (class "Default")
      (node (ref "R15") (pin "2") (pinfunction "2_2") (pintype "passive"))
      (node (ref "U$25") (pin "P9") (pinfunction "Q7S_P9") (pintype "bidirectional"))
      (node (ref "U$26") (pin "P14") (pinfunction "DS_P14") (pintype "bidirectional"))
    )
    (net (code "54") (name "Net-(U$26-MR)") (class "Default")
      (node (ref "C11") (pin "2") (pinfunction "2_2") (pintype "passive"))
      (node (ref "R12") (pin "2") (pinfunction "2_2") (pintype "passive"))
      (node (ref "U$26") (pin "P10") (pinfunction "MR_P10") (pintype "bidirectional"))
    )
    (net (code "55") (name "Net-(U1-BDS)") (class "Default")
      (node (ref "C2") (pin "2") (pinfunction "2_2") (pintype "passive"))
      (node (ref "U1") (pin "5") (pinfunction "BDS_5") (pintype "bidirectional"))
    )
    (net (code "56") (name "Net-(U1-COMP)") (class "Default")
      (node (ref "C1") (pin "2") (pinfunction "2_2") (pintype "passive"))
      (node (ref "U1") (pin "3") (pinfunction "COMP_3") (pintype "bidirectional"))
    )
    (net (code "57") (name "Net-(U1-EN)") (class "Default")
      (node (ref "T1") (pin "E") (pinfunction "E_E") (pintype "passive"))
      (node (ref "U1") (pin "7") (pinfunction "EN_7") (pintype "bidirectional"))
      (node (ref "U1") (pin "8") (pinfunction "VS_8") (pintype "bidirectional"))
    )
    (net (code "58") (name "PHA_A") (class "Default")
      (node (ref "U$1") (pin "P11") (pinfunction "0_P11") (pintype "bidirectional"))
      (node (ref "U$2") (pin "3") (pinfunction "PHA_A_3") (pintype "bidirectional"))
    )
    (net (code "59") (name "PHA_B") (class "Default")
      (node (ref "U$1") (pin "P13") (pinfunction "2_P13") (pintype "bidirectional"))
      (node (ref "U$2") (pin "7") (pinfunction "PHA_B_7") (pintype "bidirectional"))
    )
    (net (code "60") (name "PWR1") (class "Default")
      (node (ref "B1") (pin "PWR1_1") (pinfunction "PWR1_PWR1_1") (pintype "passive"))
      (node (ref "B1") (pin "PWR1_2") (pinfunction "PWR1_PWR1_2") (pintype "passive"))
      (node (ref "B2") (pin "PWR1_1") (pinfunction "PWR1_PWR1_1") (pintype "passive"))
      (node (ref "B2") (pin "PWR1_2") (pinfunction "PWR1_PWR1_2") (pintype "passive"))
      (node (ref "B3") (pin "PWR1_1") (pinfunction "PWR1_PWR1_1") (pintype "passive"))
      (node (ref "B3") (pin "PWR1_2") (pinfunction "PWR1_PWR1_2") (pintype "passive"))
      (node (ref "B4") (pin "PWR1_1") (pinfunction "PWR1_PWR1_1") (pintype "passive"))
      (node (ref "B4") (pin "PWR1_2") (pinfunction "PWR1_PWR1_2") (pintype "passive"))
      (node (ref "B5") (pin "PWR1_1") (pinfunction "PWR1_PWR1_1") (pintype "passive"))
      (node (ref "B5") (pin "PWR1_2") (pinfunction "PWR1_PWR1_2") (pintype "passive"))
      (node (ref "B6") (pin "PWR1_1") (pinfunction "PWR1_PWR1_1") (pintype "passive"))
      (node (ref "B6") (pin "PWR1_2") (pinfunction "PWR1_PWR1_2") (pintype "passive"))
      (node (ref "U$17") (pin "P$1") (pinfunction "P$1_P$1") (pintype "bidirectional"))
      (node (ref "U$17") (pin "P$2") (pinfunction "P$1_P$2") (pintype "bidirectional"))
      (node (ref "U$8") (pin "2") (pinfunction "A_2") (pintype "passive"))
    )
    (net (code "61") (name "PWR2") (class "Default")
      (node (ref "B1") (pin "PWR2_1") (pinfunction "PWR2_PWR2_1") (pintype "passive"))
      (node (ref "B1") (pin "PWR2_2") (pinfunction "PWR2_PWR2_2") (pintype "passive"))
      (node (ref "B2") (pin "PWR2_1") (pinfunction "PWR2_PWR2_1") (pintype "passive"))
      (node (ref "B2") (pin "PWR2_2") (pinfunction "PWR2_PWR2_2") (pintype "passive"))
      (node (ref "B3") (pin "PWR2_1") (pinfunction "PWR2_PWR2_1") (pintype "passive"))
      (node (ref "B3") (pin "PWR2_2") (pinfunction "PWR2_PWR2_2") (pintype "passive"))
      (node (ref "B4") (pin "PWR2_1") (pinfunction "PWR2_PWR2_1") (pintype "passive"))
      (node (ref "B4") (pin "PWR2_2") (pinfunction "PWR2_PWR2_2") (pintype "passive"))
      (node (ref "B5") (pin "PWR2_1") (pinfunction "PWR2_PWR2_1") (pintype "passive"))
      (node (ref "B5") (pin "PWR2_2") (pinfunction "PWR2_PWR2_2") (pintype "passive"))
      (node (ref "B6") (pin "PWR2_1") (pinfunction "PWR2_PWR2_1") (pintype "passive"))
      (node (ref "B6") (pin "PWR2_2") (pinfunction "PWR2_PWR2_2") (pintype "passive"))
      (node (ref "U$19") (pin "P$1") (pinfunction "P$1_P$1") (pintype "bidirectional"))
      (node (ref "U$19") (pin "P$2") (pinfunction "P$1_P$2") (pintype "bidirectional"))
      (node (ref "U$9") (pin "2") (pinfunction "A_2") (pintype "passive"))
    )
    (net (code "62") (name "SC0") (class "Default")
      (node (ref "B2") (pin "P4") (pinfunction "P4_P4") (pintype "bidirectional"))
      (node (ref "B3") (pin "P4") (pinfunction "P4_P4") (pintype "bidirectional"))
      (node (ref "B4") (pin "P4") (pinfunction "P4_P4") (pintype "bidirectional"))
      (node (ref "R4") (pin "1") (pinfunction "1_1") (pintype "passive"))
      (node (ref "U$21") (pin "5") (pinfunction "SC0_5") (pintype "bidirectional"))
    )
    (net (code "63") (name "SC1") (class "Default")
      (node (ref "B1") (pin "P4") (pinfunction "P4_P4") (pintype "bidirectional"))
      (node (ref "B5") (pin "P4") (pinfunction "P4_P4") (pintype "bidirectional"))
      (node (ref "B6") (pin "P4") (pinfunction "P4_P4") (pintype "bidirectional"))
      (node (ref "R6") (pin "1") (pinfunction "1_1") (pintype "passive"))
      (node (ref "U$21") (pin "8") (pinfunction "SC1_8") (pintype "bidirectional"))
    )
    (net (code "64") (name "SCK") (class "Default")
      (node (ref "U$1") (pin "P23") (pinfunction "14_P23") (pintype "bidirectional"))
      (node (ref "U$11") (pin "7") (pinfunction "SCK_7") (pintype "bidirectional"))
    )
    (net (code "65") (name "SCL") (class "Default")
      (node (ref "U$1") (pin "P5") (pinfunction "9_P5") (pintype "bidirectional"))
      (node (ref "U$21") (pin "1") (pinfunction "SCL_1") (pintype "bidirectional"))
    )
    (net (code "66") (name "SD0") (class "Default")
      (node (ref "B2") (pin "P5") (pinfunction "P5_P5") (pintype "bidirectional"))
      (node (ref "B3") (pin "P5") (pinfunction "P5_P5") (pintype "bidirectional"))
      (node (ref "B4") (pin "P5") (pinfunction "P5_P5") (pintype "bidirectional"))
      (node (ref "R3") (pin "1") (pinfunction "1_1") (pintype "passive"))
      (node (ref "U$21") (pin "4") (pinfunction "SD0_4") (pintype "bidirectional"))
    )
    (net (code "67") (name "SD1") (class "Default")
      (node (ref "B1") (pin "P5") (pinfunction "P5_P5") (pintype "bidirectional"))
      (node (ref "B5") (pin "P5") (pinfunction "P5_P5") (pintype "bidirectional"))
      (node (ref "B6") (pin "P5") (pinfunction "P5_P5") (pintype "bidirectional"))
      (node (ref "R5") (pin "1") (pinfunction "1_1") (pintype "passive"))
      (node (ref "U$21") (pin "7") (pinfunction "SD1_7") (pintype "bidirectional"))
    )
    (net (code "68") (name "SDA") (class "Default")
      (node (ref "U$1") (pin "P3") (pinfunction "8_P3") (pintype "bidirectional"))
      (node (ref "U$21") (pin "2") (pinfunction "SDA_2") (pintype "bidirectional"))
    )
    (net (code "69") (name "SDO") (class "Default")
      (node (ref "R20") (pin "2") (pinfunction "2_2") (pintype "passive"))
      (node (ref "U$1") (pin "P8") (pinfunction "15_P8") (pintype "bidirectional"))
      (node (ref "U$7") (pin "P14") (pinfunction "DS_P14") (pintype "bidirectional"))
    )
    (net (code "70") (name "SHCP") (class "Default")
      (node (ref "R13") (pin "2") (pinfunction "2_2") (pintype "passive"))
      (node (ref "U$1") (pin "P18") (pinfunction "5_P18") (pintype "bidirectional"))
      (node (ref "U$22") (pin "P11") (pinfunction "SHCP_P11") (pintype "bidirectional"))
      (node (ref "U$23") (pin "P11") (pinfunction "SHCP_P11") (pintype "bidirectional"))
      (node (ref "U$24") (pin "P11") (pinfunction "SHCP_P11") (pintype "bidirectional"))
      (node (ref "U$25") (pin "P11") (pinfunction "SHCP_P11") (pintype "bidirectional"))
      (node (ref "U$26") (pin "P11") (pinfunction "SHCP_P11") (pintype "bidirectional"))
      (node (ref "U$7") (pin "P11") (pinfunction "SHCP_P11") (pintype "bidirectional"))
    )
    (net (code "71") (name "STCP") (class "Default")
      (node (ref "R14") (pin "2") (pinfunction "2_2") (pintype "passive"))
      (node (ref "U$1") (pin "P16") (pinfunction "4_P16") (pintype "bidirectional"))
      (node (ref "U$22") (pin "P12") (pinfunction "STCP_P12") (pintype "bidirectional"))
      (node (ref "U$23") (pin "P12") (pinfunction "STCP_P12") (pintype "bidirectional"))
      (node (ref "U$24") (pin "P12") (pinfunction "STCP_P12") (pintype "bidirectional"))
      (node (ref "U$25") (pin "P12") (pinfunction "STCP_P12") (pintype "bidirectional"))
      (node (ref "U$26") (pin "P12") (pinfunction "STCP_P12") (pintype "bidirectional"))
      (node (ref "U$7") (pin "P12") (pinfunction "STCP_P12") (pintype "bidirectional"))
    )
    (net (code "72") (name "unconnected-(U$1-1-PadP12)") (class "Default")
      (node (ref "U$1") (pin "P12") (pinfunction "1_P12") (pintype "bidirectional"))
    )
    (net (code "73") (name "unconnected-(U$1-3V3-PadP1)") (class "Default")
      (node (ref "U$1") (pin "P1") (pinfunction "3V3_P1") (pintype "bidirectional"))
    )
    (net (code "74") (name "unconnected-(U$1-6-PadP22)") (class "Default")
      (node (ref "U$1") (pin "P22") (pinfunction "6_P22") (pintype "bidirectional"))
    )
    (net (code "75") (name "unconnected-(U$1-7-PadP7)") (class "Default")
      (node (ref "U$1") (pin "P7") (pinfunction "7_P7") (pintype "bidirectional"))
    )
    (net (code "76") (name "unconnected-(U$1-11-PadP26)") (class "Default")
      (node (ref "U$1") (pin "P26") (pinfunction "11_P26") (pintype "bidirectional"))
    )
    (net (code "77") (name "unconnected-(U$1-16-PadP10)") (class "Default")
      (node (ref "U$1") (pin "P10") (pinfunction "16_P10") (pintype "bidirectional"))
    )
    (net (code "78") (name "unconnected-(U$1-22-PadP31)") (class "Default")
      (node (ref "U$1") (pin "P31") (pinfunction "22_P31") (pintype "bidirectional"))
    )
    (net (code "79") (name "unconnected-(U$1-23-PadP33)") (class "Default")
      (node (ref "U$1") (pin "P33") (pinfunction "23_P33") (pintype "bidirectional"))
    )
    (net (code "80") (name "unconnected-(U$1-24-PadP35)") (class "Default")
      (node (ref "U$1") (pin "P35") (pinfunction "24_P35") (pintype "bidirectional"))
    )
    (net (code "81") (name "unconnected-(U$1-25-PadP37)") (class "Default")
      (node (ref "U$1") (pin "P37") (pinfunction "25_P37") (pintype "bidirectional"))
    )
    (net (code "82") (name "unconnected-(U$1-26-PadP32)") (class "Default")
      (node (ref "U$1") (pin "P32") (pinfunction "26_P32") (pintype "bidirectional"))
    )
    (net (code "83") (name "unconnected-(U$1-27-PadP36)") (class "Default")
      (node (ref "U$1") (pin "P36") (pinfunction "27_P36") (pintype "bidirectional"))
    )
    (net (code "84") (name "unconnected-(U$1-28-PadP38)") (class "Default")
      (node (ref "U$1") (pin "P38") (pinfunction "28_P38") (pintype "bidirectional"))
    )
    (net (code "85") (name "unconnected-(U$1-29-PadP40)") (class "Default")
      (node (ref "U$1") (pin "P40") (pinfunction "29_P40") (pintype "bidirectional"))
    )
    (net (code "86") (name "unconnected-(U$1-30-PadP27)") (class "Default")
      (node (ref "U$1") (pin "P27") (pinfunction "30_P27") (pintype "bidirectional"))
    )
    (net (code "87") (name "unconnected-(U$1-31-PadP28)") (class "Default")
      (node (ref "U$1") (pin "P28") (pinfunction "31_P28") (pintype "bidirectional"))
    )
    (net (code "88") (name "unconnected-(U$7-Q0-PadP15)") (class "Default")
      (node (ref "U$7") (pin "P15") (pinfunction "Q0_P15") (pintype "bidirectional"))
    )
    (net (code "89") (name "unconnected-(U$7-Q1-PadP1)") (class "Default")
      (node (ref "U$7") (pin "P1") (pinfunction "Q1_P1") (pintype "bidirectional"))
    )
    (net (code "90") (name "unconnected-(U$7-Q2-PadP2)") (class "Default")
      (node (ref "U$7") (pin "P2") (pinfunction "Q2_P2") (pintype "bidirectional"))
    )
    (net (code "91") (name "unconnected-(U$7-Q3-PadP3)") (class "Default")
      (node (ref "U$7") (pin "P3") (pinfunction "Q3_P3") (pintype "bidirectional"))
    )
    (net (code "92") (name "unconnected-(U$22-Q0-PadP15)") (class "Default")
      (node (ref "U$22") (pin "P15") (pinfunction "Q0_P15") (pintype "bidirectional"))
    )
    (net (code "93") (name "unconnected-(U$22-Q1-PadP1)") (class "Default")
      (node (ref "U$22") (pin "P1") (pinfunction "Q1_P1") (pintype "bidirectional"))
    )
    (net (code "94") (name "unconnected-(U$22-Q2-PadP2)") (class "Default")
      (node (ref "U$22") (pin "P2") (pinfunction "Q2_P2") (pintype "bidirectional"))
    )
    (net (code "95") (name "unconnected-(U$22-Q3-PadP3)") (class "Default")
      (node (ref "U$22") (pin "P3") (pinfunction "Q3_P3") (pintype "bidirectional"))
    )
    (net (code "96") (name "unconnected-(U$23-Q0-PadP15)") (class "Default")
      (node (ref "U$23") (pin "P15") (pinfunction "Q0_P15") (pintype "bidirectional"))
    )
    (net (code "97") (name "unconnected-(U$23-Q1-PadP1)") (class "Default")
      (node (ref "U$23") (pin "P1") (pinfunction "Q1_P1") (pintype "bidirectional"))
    )
    (net (code "98") (name "unconnected-(U$23-Q2-PadP2)") (class "Default")
      (node (ref "U$23") (pin "P2") (pinfunction "Q2_P2") (pintype "bidirectional"))
    )
    (net (code "99") (name "unconnected-(U$23-Q3-PadP3)") (class "Default")
      (node (ref "U$23") (pin "P3") (pinfunction "Q3_P3") (pintype "bidirectional"))
    )
    (net (code "100") (name "unconnected-(U$24-Q0-PadP15)") (class "Default")
      (node (ref "U$24") (pin "P15") (pinfunction "Q0_P15") (pintype "bidirectional"))
    )
    (net (code "101") (name "unconnected-(U$24-Q1-PadP1)") (class "Default")
      (node (ref "U$24") (pin "P1") (pinfunction "Q1_P1") (pintype "bidirectional"))
    )
    (net (code "102") (name "unconnected-(U$24-Q2-PadP2)") (class "Default")
      (node (ref "U$24") (pin "P2") (pinfunction "Q2_P2") (pintype "bidirectional"))
    )
    (net (code "103") (name "unconnected-(U$24-Q3-PadP3)") (class "Default")
      (node (ref "U$24") (pin "P3") (pinfunction "Q3_P3") (pintype "bidirectional"))
    )
    (net (code "104") (name "unconnected-(U$25-Q0-PadP15)") (class "Default")
      (node (ref "U$25") (pin "P15") (pinfunction "Q0_P15") (pintype "bidirectional"))
    )
    (net (code "105") (name "unconnected-(U$25-Q1-PadP1)") (class "Default")
      (node (ref "U$25") (pin "P1") (pinfunction "Q1_P1") (pintype "bidirectional"))
    )
    (net (code "106") (name "unconnected-(U$25-Q2-PadP2)") (class "Default")
      (node (ref "U$25") (pin "P2") (pinfunction "Q2_P2") (pintype "bidirectional"))
    )
    (net (code "107") (name "unconnected-(U$25-Q3-PadP3)") (class "Default")
      (node (ref "U$25") (pin "P3") (pinfunction "Q3_P3") (pintype "bidirectional"))
    )
    (net (code "108") (name "unconnected-(U$26-Q0-PadP15)") (class "Default")
      (node (ref "U$26") (pin "P15") (pinfunction "Q0_P15") (pintype "bidirectional"))
    )
    (net (code "109") (name "unconnected-(U$26-Q1-PadP1)") (class "Default")
      (node (ref "U$26") (pin "P1") (pinfunction "Q1_P1") (pintype "bidirectional"))
    )
    (net (code "110") (name "unconnected-(U$26-Q2-PadP2)") (class "Default")
      (node (ref "U$26") (pin "P2") (pinfunction "Q2_P2") (pintype "bidirectional"))
    )
    (net (code "111") (name "unconnected-(U$26-Q3-PadP3)") (class "Default")
      (node (ref "U$26") (pin "P3") (pinfunction "Q3_P3") (pintype "bidirectional"))
    )
    (net (code "112") (name "unconnected-(U$26-Q7S-PadP9)") (class "Default")
      (node (ref "U$26") (pin "P9") (pinfunction "Q7S_P9") (pintype "bidirectional"))
    )
  )
)
